# PC_ESP8266_Shield.net
KiCad netlist of a schematic drawn in EAGLE
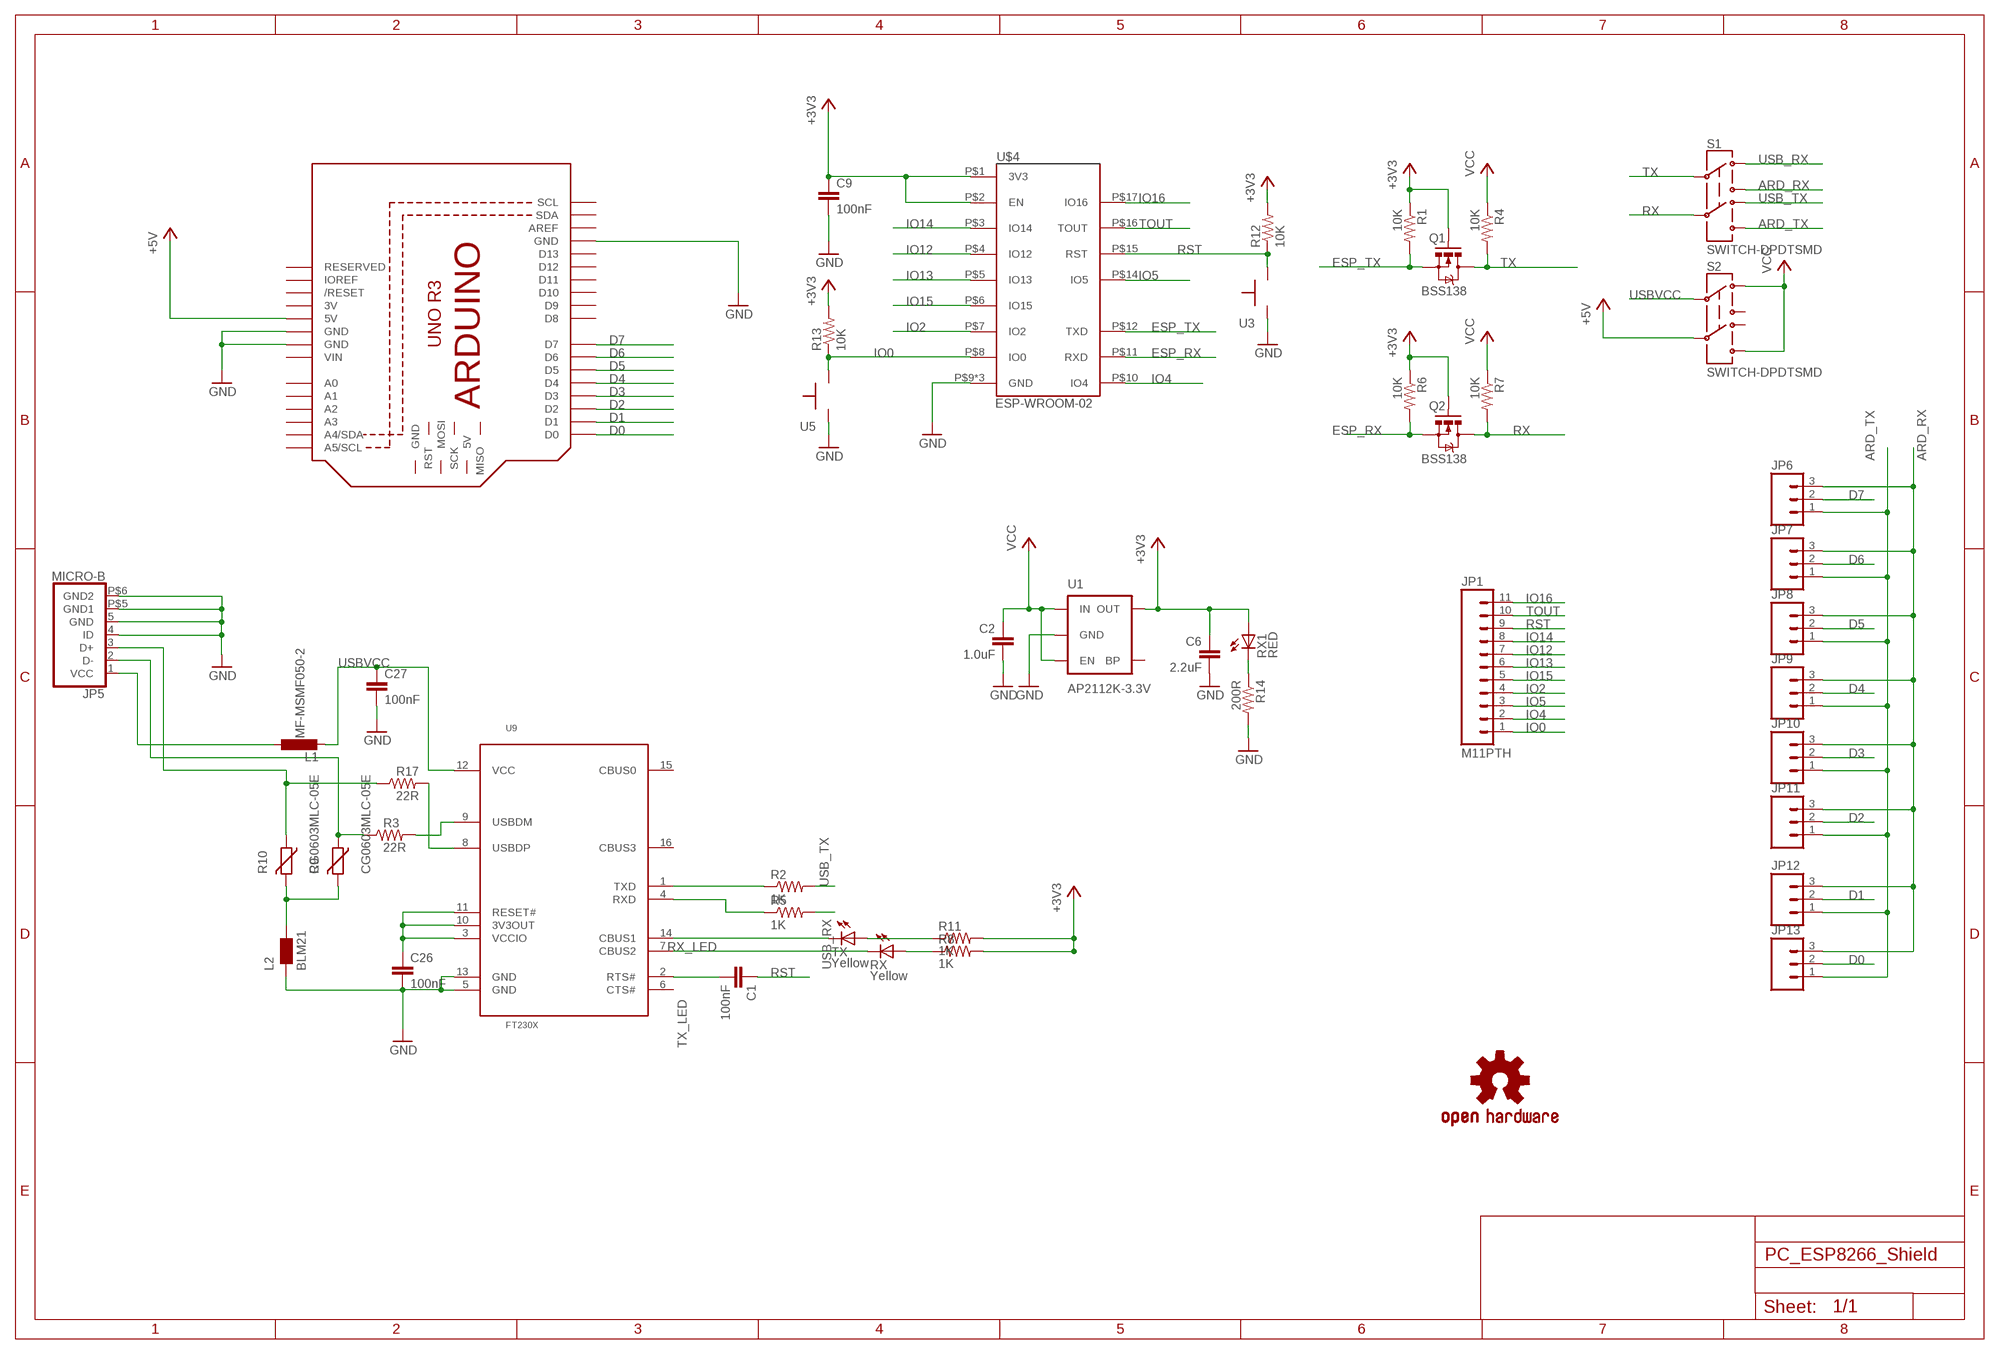
[diagram p0: schematic, sheet 1]

(export (version "E")
  (design (tool "Eeschema 10.0.6"))
  (components
    (comp (ref "C1")
      (value "100nF")
      (footprint "eagle-import:C0805")
      (libsource (lib "eagle-import") (part "C-EUC0805"))
    )
    (comp (ref "C2")
      (value "1.0uF")
      (footprint "eagle-import:0805")
      (libsource (lib "eagle-import") (part "1.0UF-25V-+80/-20(0805)"))
    )
    (comp (ref "C6")
      (value "2.2uF")
      (footprint "eagle-import:C0805")
      (libsource (lib "eagle-import") (part "C-EUC0805"))
    )
    (comp (ref "C9")
      (value "100nF")
      (footprint "eagle-import:C0805")
      (libsource (lib "eagle-import") (part "C-EUC0805"))
    )
    (comp (ref "C26")
      (value "100nF")
      (footprint "eagle-import:C0805")
      (libsource (lib "eagle-import") (part "C-EUC0805"))
    )
    (comp (ref "C27")
      (value "100nF")
      (footprint "eagle-import:C0805")
      (libsource (lib "eagle-import") (part "C-EUC0805"))
    )
    (comp (ref "JP1")
      (value "M11PTH")
      (footprint "eagle-import:1X11")
      (libsource (lib "eagle-import") (part "M11PTH"))
    )
    (comp (ref "JP5")
      (value "MICRO-B")
      (footprint "eagle-import:MICRO-B")
      (libsource (lib "eagle-import") (part "MICRO-B"))
    )
    (comp (ref "JP6")
      (value "M03PTH")
      (footprint "eagle-import:1X03")
      (libsource (lib "eagle-import") (part "M03PTH"))
    )
    (comp (ref "JP7")
      (value "M03PTH")
      (footprint "eagle-import:1X03")
      (libsource (lib "eagle-import") (part "M03PTH"))
    )
    (comp (ref "JP8")
      (value "M03PTH")
      (footprint "eagle-import:1X03")
      (libsource (lib "eagle-import") (part "M03PTH"))
    )
    (comp (ref "JP9")
      (value "M03PTH")
      (footprint "eagle-import:1X03")
      (libsource (lib "eagle-import") (part "M03PTH"))
    )
    (comp (ref "JP10")
      (value "M03PTH")
      (footprint "eagle-import:1X03")
      (libsource (lib "eagle-import") (part "M03PTH"))
    )
    (comp (ref "JP11")
      (value "M03PTH")
      (footprint "eagle-import:1X03")
      (libsource (lib "eagle-import") (part "M03PTH"))
    )
    (comp (ref "JP12")
      (value "M03PTH")
      (footprint "eagle-import:1X03")
      (libsource (lib "eagle-import") (part "M03PTH"))
    )
    (comp (ref "JP13")
      (value "M03PTH")
      (footprint "eagle-import:1X03")
      (libsource (lib "eagle-import") (part "M03PTH"))
    )
    (comp (ref "L1")
      (value "MF-MSMF050-2")
      (footprint "eagle-import:L1812")
      (libsource (lib "eagle-import") (part "L-EUL1812"))
    )
    (comp (ref "L2")
      (value "BLM21")
      (footprint "eagle-import:0805")
      (libsource (lib "eagle-import") (part "WE-CBF_0805"))
    )
    (comp (ref "Q1")
      (value "BSS138")
      (footprint "eagle-import:SOT23-3")
      (libsource (lib "eagle-import") (part "MOSFET-NCHANNELSMD"))
    )
    (comp (ref "Q2")
      (value "BSS138")
      (footprint "eagle-import:SOT23-3")
      (libsource (lib "eagle-import") (part "MOSFET-NCHANNELSMD"))
    )
    (comp (ref "R1")
      (value "10K")
      (footprint "eagle-import:R0805")
      (libsource (lib "eagle-import") (part "R-US_R0805"))
    )
    (comp (ref "R2")
      (value "1K")
      (footprint "eagle-import:R0805")
      (libsource (lib "eagle-import") (part "R-US_R0805"))
    )
    (comp (ref "R3")
      (value "22R")
      (footprint "eagle-import:R0805")
      (libsource (lib "eagle-import") (part "R-US_R0805"))
    )
    (comp (ref "R4")
      (value "10K")
      (footprint "eagle-import:R0805")
      (libsource (lib "eagle-import") (part "R-US_R0805"))
    )
    (comp (ref "R5")
      (value "1K")
      (footprint "eagle-import:R0805")
      (libsource (lib "eagle-import") (part "R-US_R0805"))
    )
    (comp (ref "R6")
      (value "10K")
      (footprint "eagle-import:R0805")
      (libsource (lib "eagle-import") (part "R-US_R0805"))
    )
    (comp (ref "R7")
      (value "10K")
      (footprint "eagle-import:R0805")
      (libsource (lib "eagle-import") (part "R-US_R0805"))
    )
    (comp (ref "R8")
      (value "1K")
      (footprint "eagle-import:R0805")
      (libsource (lib "eagle-import") (part "R-US_R0805"))
    )
    (comp (ref "R9")
      (value "CG0603MLC-05E")
      (footprint "eagle-import:CT_CN0603")
      (libsource (lib "eagle-import") (part "VARISTORCN0603"))
    )
    (comp (ref "R10")
      (value "CG0603MLC-05E")
      (footprint "eagle-import:CT_CN0603")
      (libsource (lib "eagle-import") (part "VARISTORCN0603"))
    )
    (comp (ref "R11")
      (value "1K")
      (footprint "eagle-import:R0805")
      (libsource (lib "eagle-import") (part "R-US_R0805"))
    )
    (comp (ref "R12")
      (value "10K")
      (footprint "eagle-import:R0805")
      (libsource (lib "eagle-import") (part "R-US_R0805"))
    )
    (comp (ref "R13")
      (value "10K")
      (footprint "eagle-import:R0805")
      (libsource (lib "eagle-import") (part "R-US_R0805"))
    )
    (comp (ref "R14")
      (value "200R")
      (footprint "eagle-import:R0805")
      (libsource (lib "eagle-import") (part "R-US_R0805"))
    )
    (comp (ref "R17")
      (value "22R")
      (footprint "eagle-import:R0805")
      (libsource (lib "eagle-import") (part "R-US_R0805"))
    )
    (comp (ref "RX")
      (value "Yellow")
      (footprint "eagle-import:CHIPLED_0603")
      (libsource (lib "eagle-import") (part "LEDCHIPLED_0603"))
    )
    (comp (ref "RX1")
      (value "RED")
      (footprint "eagle-import:CHIPLED_0603")
      (libsource (lib "eagle-import") (part "LEDCHIPLED_0603"))
    )
    (comp (ref "S1")
      (value "SWITCH-DPDTSMD")
      (footprint "eagle-import:AYZ0202")
      (libsource (lib "eagle-import") (part "SWITCH-DPDTSMD"))
    )
    (comp (ref "S2")
      (value "SWITCH-DPDTSMD")
      (footprint "eagle-import:AYZ0202")
      (libsource (lib "eagle-import") (part "SWITCH-DPDTSMD"))
    )
    (comp (ref "TX")
      (value "Yellow")
      (footprint "eagle-import:CHIPLED_0603")
      (libsource (lib "eagle-import") (part "LEDCHIPLED_0603"))
    )
    (comp (ref "U$1")
      (value "ARDUINO")
      (footprint "eagle-import:ARDUINO")
      (libsource (lib "eagle-import") (part "ARDUINO"))
    )
    (comp (ref "U$3")
      (value "PROTY-LOGO")
      (footprint "eagle-import:LOGO-PROTY")
      (libsource (lib "eagle-import") (part "PROTY-LOGO"))
    )
    (comp (ref "U$4")
      (value "ESP-WROOM-02")
      (footprint "eagle-import:ESP-WROOM-02")
      (libsource (lib "eagle-import") (part "ESP-WROOM-02"))
    )
    (comp (ref "U$5")
      (value "OSHW-LOGOS")
      (footprint "eagle-import:OSHW-LOGO-S")
      (libsource (lib "eagle-import") (part "OSHW-LOGOS"))
    )
    (comp (ref "U1")
      (value "AP2112K-3.3V")
      (footprint "eagle-import:SOT23-5")
      (libsource (lib "eagle-import") (part "V_REG_LDOSMD"))
    )
    (comp (ref "U3")
      (value "B3U-1000P")
      (footprint "eagle-import:B3U-1000P")
      (libsource (lib "eagle-import") (part "B3U-1000P"))
    )
    (comp (ref "U5")
      (value "B3U-1000P")
      (footprint "eagle-import:B3U-1000P")
      (libsource (lib "eagle-import") (part "B3U-1000P"))
    )
    (comp (ref "U9")
      (value "FT230X")
      (footprint "eagle-import:SSOP_16")
      (libsource (lib "eagle-import") (part "FT230X"))
    )
  )
  (nets
    (net (code "1") (name "+3V3") (class "Default")
      (node (ref "C6") (pin "1") (pinfunction "1_1") (pintype "passive"))
      (node (ref "C9") (pin "1") (pinfunction "1_1") (pintype "passive"))
      (node (ref "Q1") (pin "1") (pinfunction "G_1") (pintype "passive"))
      (node (ref "Q2") (pin "1") (pinfunction "G_1") (pintype "passive"))
      (node (ref "R1") (pin "1") (pinfunction "1_1") (pintype "passive"))
      (node (ref "R11") (pin "2") (pinfunction "2_2") (pintype "passive"))
      (node (ref "R12") (pin "2") (pinfunction "2_2") (pintype "passive"))
      (node (ref "R13") (pin "2") (pinfunction "2_2") (pintype "passive"))
      (node (ref "R6") (pin "1") (pinfunction "1_1") (pintype "passive"))
      (node (ref "R8") (pin "2") (pinfunction "2_2") (pintype "passive"))
      (node (ref "RX1") (pin "A") (pinfunction "A_A") (pintype "passive"))
      (node (ref "U$4") (pin "P$1") (pinfunction "3V3_P$1") (pintype "power_in"))
      (node (ref "U$4") (pin "P$2") (pinfunction "EN_P$2") (pintype "bidirectional"))
      (node (ref "U1") (pin "5") (pinfunction "OUT_5") (pintype "passive"))
    )
    (net (code "2") (name "+5V") (class "Default")
      (node (ref "S2") (pin "5") (pinfunction "5_5") (pintype "bidirectional"))
      (node (ref "U$1") (pin "5V") (pinfunction "5V_5V") (pintype "power_in"))
    )
    (net (code "3") (name "/3V") (class "Default")
      (node (ref "U$1") (pin "3V") (pinfunction "3V_3V") (pintype "power_in"))
    )
    (net (code "4") (name "/ARD_RX") (class "Default")
      (node (ref "JP10") (pin "3") (pinfunction "3_3") (pintype "passive"))
      (node (ref "JP11") (pin "3") (pinfunction "3_3") (pintype "passive"))
      (node (ref "JP12") (pin "3") (pinfunction "3_3") (pintype "passive"))
      (node (ref "JP13") (pin "3") (pinfunction "3_3") (pintype "passive"))
      (node (ref "JP6") (pin "3") (pinfunction "3_3") (pintype "passive"))
      (node (ref "JP7") (pin "3") (pinfunction "3_3") (pintype "passive"))
      (node (ref "JP8") (pin "3") (pinfunction "3_3") (pintype "passive"))
      (node (ref "JP9") (pin "3") (pinfunction "3_3") (pintype "passive"))
      (node (ref "S1") (pin "3") (pinfunction "3_3") (pintype "bidirectional"))
    )
    (net (code "5") (name "/ARD_TX") (class "Default")
      (node (ref "JP10") (pin "1") (pinfunction "1_1") (pintype "passive"))
      (node (ref "JP11") (pin "1") (pinfunction "1_1") (pintype "passive"))
      (node (ref "JP12") (pin "1") (pinfunction "1_1") (pintype "passive"))
      (node (ref "JP13") (pin "1") (pinfunction "1_1") (pintype "passive"))
      (node (ref "JP6") (pin "1") (pinfunction "1_1") (pintype "passive"))
      (node (ref "JP7") (pin "1") (pinfunction "1_1") (pintype "passive"))
      (node (ref "JP8") (pin "1") (pinfunction "1_1") (pintype "passive"))
      (node (ref "JP9") (pin "1") (pinfunction "1_1") (pintype "passive"))
      (node (ref "S1") (pin "6") (pinfunction "6_6") (pintype "bidirectional"))
    )
    (net (code "6") (name "/D0") (class "Default")
      (node (ref "JP13") (pin "2") (pinfunction "2_2") (pintype "passive"))
      (node (ref "U$1") (pin "D0") (pinfunction "D0_D0") (pintype "bidirectional"))
    )
    (net (code "7") (name "/D1") (class "Default")
      (node (ref "JP12") (pin "2") (pinfunction "2_2") (pintype "passive"))
      (node (ref "U$1") (pin "D1") (pinfunction "D1_D1") (pintype "bidirectional"))
    )
    (net (code "8") (name "/D2") (class "Default")
      (node (ref "JP11") (pin "2") (pinfunction "2_2") (pintype "passive"))
      (node (ref "U$1") (pin "D2") (pinfunction "D2_D2") (pintype "bidirectional"))
    )
    (net (code "9") (name "/D3") (class "Default")
      (node (ref "JP10") (pin "2") (pinfunction "2_2") (pintype "passive"))
      (node (ref "U$1") (pin "D3") (pinfunction "D3_D3") (pintype "bidirectional"))
    )
    (net (code "10") (name "/D4") (class "Default")
      (node (ref "JP9") (pin "2") (pinfunction "2_2") (pintype "passive"))
      (node (ref "U$1") (pin "D4") (pinfunction "D4_D4") (pintype "bidirectional"))
    )
    (net (code "11") (name "/D5") (class "Default")
      (node (ref "JP8") (pin "2") (pinfunction "2_2") (pintype "passive"))
      (node (ref "U$1") (pin "D5") (pinfunction "D5_D5") (pintype "bidirectional"))
    )
    (net (code "12") (name "/D6") (class "Default")
      (node (ref "JP7") (pin "2") (pinfunction "2_2") (pintype "passive"))
      (node (ref "U$1") (pin "D6") (pinfunction "D6_D6") (pintype "bidirectional"))
    )
    (net (code "13") (name "/D7") (class "Default")
      (node (ref "JP6") (pin "2") (pinfunction "2_2") (pintype "passive"))
      (node (ref "U$1") (pin "D7") (pinfunction "D7_D7") (pintype "bidirectional"))
    )
    (net (code "14") (name "/ESP_RX") (class "Default")
      (node (ref "Q2") (pin "2") (pinfunction "S_2") (pintype "passive"))
      (node (ref "R6") (pin "2") (pinfunction "2_2") (pintype "passive"))
      (node (ref "U$4") (pin "P$11") (pinfunction "RXD_P$11") (pintype "input"))
    )
    (net (code "15") (name "/ESP_TX") (class "Default")
      (node (ref "Q1") (pin "2") (pinfunction "S_2") (pintype "passive"))
      (node (ref "R1") (pin "2") (pinfunction "2_2") (pintype "passive"))
      (node (ref "U$4") (pin "P$12") (pinfunction "TXD_P$12") (pintype "output"))
    )
    (net (code "16") (name "/IO0") (class "Default")
      (node (ref "JP1") (pin "1") (pinfunction "1_1") (pintype "passive"))
      (node (ref "R13") (pin "1") (pinfunction "1_1") (pintype "passive"))
      (node (ref "U$4") (pin "P$8") (pinfunction "IO0_P$8") (pintype "bidirectional"))
      (node (ref "U5") (pin "P$2") (pinfunction "P$2_P$2") (pintype "bidirectional"))
    )
    (net (code "17") (name "/IO2") (class "Default")
      (node (ref "JP1") (pin "4") (pinfunction "4_4") (pintype "passive"))
      (node (ref "U$4") (pin "P$7") (pinfunction "IO2_P$7") (pintype "bidirectional"))
    )
    (net (code "18") (name "/IO4") (class "Default")
      (node (ref "JP1") (pin "2") (pinfunction "2_2") (pintype "passive"))
      (node (ref "U$4") (pin "P$10") (pinfunction "IO4_P$10") (pintype "bidirectional"))
    )
    (net (code "19") (name "/IO5") (class "Default")
      (node (ref "JP1") (pin "3") (pinfunction "3_3") (pintype "passive"))
      (node (ref "U$4") (pin "P$14") (pinfunction "IO5_P$14") (pintype "bidirectional"))
    )
    (net (code "20") (name "/IO12") (class "Default")
      (node (ref "JP1") (pin "7") (pinfunction "7_7") (pintype "passive"))
      (node (ref "U$4") (pin "P$4") (pinfunction "IO12_P$4") (pintype "bidirectional"))
    )
    (net (code "21") (name "/IO13") (class "Default")
      (node (ref "JP1") (pin "6") (pinfunction "6_6") (pintype "passive"))
      (node (ref "U$4") (pin "P$5") (pinfunction "IO13_P$5") (pintype "bidirectional"))
    )
    (net (code "22") (name "/IO14") (class "Default")
      (node (ref "JP1") (pin "8") (pinfunction "8_8") (pintype "passive"))
      (node (ref "U$4") (pin "P$3") (pinfunction "IO14_P$3") (pintype "bidirectional"))
    )
    (net (code "23") (name "/IO15") (class "Default")
      (node (ref "JP1") (pin "5") (pinfunction "5_5") (pintype "passive"))
      (node (ref "U$4") (pin "P$6") (pinfunction "IO15_P$6") (pintype "bidirectional"))
    )
    (net (code "24") (name "/IO16") (class "Default")
      (node (ref "JP1") (pin "11") (pinfunction "11_11") (pintype "passive"))
      (node (ref "U$4") (pin "P$17") (pinfunction "IO16_P$17") (pintype "bidirectional"))
    )
    (net (code "25") (name "/RST") (class "Default")
      (node (ref "C1") (pin "1") (pinfunction "1_1") (pintype "passive"))
      (node (ref "JP1") (pin "9") (pinfunction "9_9") (pintype "passive"))
      (node (ref "R12") (pin "1") (pinfunction "1_1") (pintype "passive"))
      (node (ref "U$4") (pin "P$15") (pinfunction "RST_P$15") (pintype "bidirectional"))
      (node (ref "U3") (pin "P$2") (pinfunction "P$2_P$2") (pintype "bidirectional"))
    )
    (net (code "26") (name "/RX") (class "Default")
      (node (ref "Q2") (pin "3") (pinfunction "D_3") (pintype "passive"))
      (node (ref "R7") (pin "2") (pinfunction "2_2") (pintype "passive"))
      (node (ref "S1") (pin "5") (pinfunction "5_5") (pintype "bidirectional"))
    )
    (net (code "27") (name "/RX_LED") (class "Default")
      (node (ref "RX") (pin "C") (pinfunction "C_C") (pintype "passive"))
      (node (ref "U9") (pin "7") (pinfunction "CBUS2_7") (pintype "bidirectional"))
    )
    (net (code "28") (name "/TOUT") (class "Default")
      (node (ref "JP1") (pin "10") (pinfunction "10_10") (pintype "passive"))
      (node (ref "U$4") (pin "P$16") (pinfunction "TOUT_P$16") (pintype "bidirectional"))
    )
    (net (code "29") (name "/TX") (class "Default")
      (node (ref "Q1") (pin "3") (pinfunction "D_3") (pintype "passive"))
      (node (ref "R4") (pin "2") (pinfunction "2_2") (pintype "passive"))
      (node (ref "S1") (pin "2") (pinfunction "2_2") (pintype "bidirectional"))
    )
    (net (code "30") (name "/TX_LED") (class "Default")
      (node (ref "TX") (pin "C") (pinfunction "C_C") (pintype "passive"))
      (node (ref "U9") (pin "14") (pinfunction "CBUS1_14") (pintype "bidirectional"))
    )
    (net (code "31") (name "/USBVCC") (class "Default")
      (node (ref "C27") (pin "1") (pinfunction "1_1") (pintype "passive"))
      (node (ref "L1") (pin "2") (pinfunction "2_2") (pintype "passive"))
      (node (ref "S2") (pin "2") (pinfunction "2_2") (pintype "bidirectional"))
      (node (ref "U9") (pin "12") (pinfunction "VCC_12") (pintype "bidirectional"))
    )
    (net (code "32") (name "/USB_RX") (class "Default")
      (node (ref "R5") (pin "2") (pinfunction "2_2") (pintype "passive"))
      (node (ref "S1") (pin "1") (pinfunction "1_1") (pintype "bidirectional"))
    )
    (net (code "33") (name "/USB_TX") (class "Default")
      (node (ref "R2") (pin "2") (pinfunction "2_2") (pintype "passive"))
      (node (ref "S1") (pin "4") (pinfunction "4_4") (pintype "bidirectional"))
    )
    (net (code "34") (name "/VIN") (class "Default")
      (node (ref "U$1") (pin "VIN") (pinfunction "VIN_VIN") (pintype "power_in"))
    )
    (net (code "35") (name "GND") (class "Default")
      (node (ref "C2") (pin "2") (pinfunction "2_2") (pintype "passive"))
      (node (ref "C26") (pin "2") (pinfunction "2_2") (pintype "passive"))
      (node (ref "C27") (pin "2") (pinfunction "2_2") (pintype "passive"))
      (node (ref "C6") (pin "2") (pinfunction "2_2") (pintype "passive"))
      (node (ref "C9") (pin "2") (pinfunction "2_2") (pintype "passive"))
      (node (ref "JP5") (pin "4") (pinfunction "ID_4") (pintype "bidirectional"))
      (node (ref "JP5") (pin "5") (pinfunction "GND_5") (pintype "bidirectional"))
      (node (ref "JP5") (pin "P$5") (pinfunction "GND1_P$5") (pintype "bidirectional"))
      (node (ref "JP5") (pin "P$6") (pinfunction "GND2_P$6") (pintype "bidirectional"))
      (node (ref "L2") (pin "1") (pinfunction "1_1") (pintype "passive"))
      (node (ref "R14") (pin "2") (pinfunction "2_2") (pintype "passive"))
      (node (ref "U$1") (pin "GND") (pinfunction "GND_GND") (pintype "power_in"))
      (node (ref "U$1") (pin "GND@1") (pinfunction "GND_GND@1") (pintype "power_in"))
      (node (ref "U$1") (pin "GND@2") (pinfunction "GND_GND@2") (pintype "power_in"))
      (node (ref "U$4") (pin "P$13") (pinfunction "GND_P$13") (pintype "power_in"))
      (node (ref "U$4") (pin "P$18") (pinfunction "GND_P$18") (pintype "power_in"))
      (node (ref "U$4") (pin "P$9") (pinfunction "GND_P$9") (pintype "power_in"))
      (node (ref "U1") (pin "2") (pinfunction "GND_2") (pintype "input"))
      (node (ref "U3") (pin "P$1") (pinfunction "P$1_P$1") (pintype "bidirectional"))
      (node (ref "U5") (pin "P$1") (pinfunction "P$1_P$1") (pintype "bidirectional"))
      (node (ref "U9") (pin "13") (pinfunction "GND_13") (pintype "bidirectional"))
      (node (ref "U9") (pin "5") (pinfunction "GND_5") (pintype "bidirectional"))
    )
    (net (code "36") (name "Net-(JP5-D+)") (class "Default")
      (node (ref "JP5") (pin "3") (pinfunction "D+_3") (pintype "bidirectional"))
      (node (ref "R10") (pin "1") (pinfunction "1_1") (pintype "passive"))
      (node (ref "R17") (pin "1") (pinfunction "1_1") (pintype "passive"))
    )
    (net (code "37") (name "Net-(JP5-D-)") (class "Default")
      (node (ref "JP5") (pin "2") (pinfunction "D-_2") (pintype "bidirectional"))
      (node (ref "R3") (pin "1") (pinfunction "1_1") (pintype "passive"))
      (node (ref "R9") (pin "1") (pinfunction "1_1") (pintype "passive"))
    )
    (net (code "38") (name "Net-(JP5-VCC)") (class "Default")
      (node (ref "JP5") (pin "1") (pinfunction "VCC_1") (pintype "bidirectional"))
      (node (ref "L1") (pin "1") (pinfunction "1_1") (pintype "passive"))
    )
    (net (code "39") (name "Net-(L2-Pad2)") (class "Default")
      (node (ref "L2") (pin "2") (pinfunction "2_2") (pintype "passive"))
      (node (ref "R10") (pin "2") (pinfunction "2_2") (pintype "passive"))
      (node (ref "R9") (pin "2") (pinfunction "2_2") (pintype "passive"))
    )
    (net (code "40") (name "Net-(R8-Pad1)") (class "Default")
      (node (ref "R8") (pin "1") (pinfunction "1_1") (pintype "passive"))
      (node (ref "RX") (pin "A") (pinfunction "A_A") (pintype "passive"))
    )
    (net (code "41") (name "Net-(R11-Pad1)") (class "Default")
      (node (ref "R11") (pin "1") (pinfunction "1_1") (pintype "passive"))
      (node (ref "TX") (pin "A") (pinfunction "A_A") (pintype "passive"))
    )
    (net (code "42") (name "Net-(R14-Pad1)") (class "Default")
      (node (ref "R14") (pin "1") (pinfunction "1_1") (pintype "passive"))
      (node (ref "RX1") (pin "C") (pinfunction "C_C") (pintype "passive"))
    )
    (net (code "43") (name "Net-(U9-3V3OUT)") (class "Default")
      (node (ref "C26") (pin "1") (pinfunction "1_1") (pintype "passive"))
      (node (ref "U9") (pin "10") (pinfunction "3V3OUT_10") (pintype "bidirectional"))
      (node (ref "U9") (pin "11") (pinfunction "RESET#_11") (pintype "bidirectional"))
      (node (ref "U9") (pin "3") (pinfunction "VCCIO_3") (pintype "bidirectional"))
    )
    (net (code "44") (name "Net-(U9-RTS#)") (class "Default")
      (node (ref "C1") (pin "2") (pinfunction "2_2") (pintype "passive"))
      (node (ref "U9") (pin "2") (pinfunction "RTS#_2") (pintype "bidirectional"))
    )
    (net (code "45") (name "Net-(U9-RXD)") (class "Default")
      (node (ref "R5") (pin "1") (pinfunction "1_1") (pintype "passive"))
      (node (ref "U9") (pin "4") (pinfunction "RXD_4") (pintype "bidirectional"))
    )
    (net (code "46") (name "Net-(U9-TXD)") (class "Default")
      (node (ref "R2") (pin "1") (pinfunction "1_1") (pintype "passive"))
      (node (ref "U9") (pin "1") (pinfunction "TXD_1") (pintype "bidirectional"))
    )
    (net (code "47") (name "Net-(U9-USBDM)") (class "Default")
      (node (ref "R3") (pin "2") (pinfunction "2_2") (pintype "passive"))
      (node (ref "U9") (pin "9") (pinfunction "USBDM_9") (pintype "bidirectional"))
    )
    (net (code "48") (name "Net-(U9-USBDP)") (class "Default")
      (node (ref "R17") (pin "2") (pinfunction "2_2") (pintype "passive"))
      (node (ref "U9") (pin "8") (pinfunction "USBDP_8") (pintype "bidirectional"))
    )
    (net (code "49") (name "VCC") (class "Default")
      (node (ref "C2") (pin "1") (pinfunction "1_1") (pintype "passive"))
      (node (ref "R4") (pin "1") (pinfunction "1_1") (pintype "passive"))
      (node (ref "R7") (pin "1") (pinfunction "1_1") (pintype "passive"))
      (node (ref "S2") (pin "1") (pinfunction "1_1") (pintype "bidirectional"))
      (node (ref "S2") (pin "6") (pinfunction "6_6") (pintype "bidirectional"))
      (node (ref "U1") (pin "1") (pinfunction "IN_1") (pintype "input"))
      (node (ref "U1") (pin "3") (pinfunction "EN_3") (pintype "input"))
    )
    (net (code "50") (name "unconnected-(S2-Pad3)") (class "Default")
      (node (ref "S2") (pin "3") (pinfunction "3_3") (pintype "bidirectional"))
    )
    (net (code "51") (name "unconnected-(S2-Pad4)") (class "Default")
      (node (ref "S2") (pin "4") (pinfunction "4_4") (pintype "bidirectional"))
    )
    (net (code "52") (name "unconnected-(U$1-5V-Pad5V_ICSP)") (class "Default")
      (node (ref "U$1") (pin "5V_ICSP") (pinfunction "5V_5V_ICSP") (pintype "passive"))
    )
    (net (code "53") (name "unconnected-(U$1-A4{slash}SDA-PadA4)") (class "Default")
      (node (ref "U$1") (pin "A4") (pinfunction "A4/SDA_A4") (pintype "bidirectional"))
    )
    (net (code "54") (name "unconnected-(U$1-A5{slash}SCL-PadA5)") (class "Default")
      (node (ref "U$1") (pin "A5") (pinfunction "A5/SCL_A5") (pintype "bidirectional"))
    )
    (net (code "55") (name "unconnected-(U$1-GND-PadGND@3)") (class "Default")
      (node (ref "U$1") (pin "GND@3") (pinfunction "GND_GND@3") (pintype "passive"))
    )
    (net (code "56") (name "unconnected-(U$1-PadA0)") (class "Default")
      (node (ref "U$1") (pin "A0") (pinfunction "A0_A0") (pintype "bidirectional"))
    )
    (net (code "57") (name "unconnected-(U$1-PadA1)") (class "Default")
      (node (ref "U$1") (pin "A1") (pinfunction "A1_A1") (pintype "bidirectional"))
    )
    (net (code "58") (name "unconnected-(U$1-PadA2)") (class "Default")
      (node (ref "U$1") (pin "A2") (pinfunction "A2_A2") (pintype "bidirectional"))
    )
    (net (code "59") (name "unconnected-(U$1-PadA3)") (class "Default")
      (node (ref "U$1") (pin "A3") (pinfunction "A3_A3") (pintype "bidirectional"))
    )
    (net (code "60") (name "unconnected-(U$1-PadAREF)") (class "Default")
      (node (ref "U$1") (pin "AREF") (pinfunction "AREF_AREF") (pintype "bidirectional"))
    )
    (net (code "61") (name "unconnected-(U$1-PadD8)") (class "Default")
      (node (ref "U$1") (pin "D8") (pinfunction "D8_D8") (pintype "bidirectional"))
    )
    (net (code "62") (name "unconnected-(U$1-PadD9)") (class "Default")
      (node (ref "U$1") (pin "D9") (pinfunction "D9_D9") (pintype "bidirectional"))
    )
    (net (code "63") (name "unconnected-(U$1-PadD10)") (class "Default")
      (node (ref "U$1") (pin "D10") (pinfunction "D10_D10") (pintype "bidirectional"))
    )
    (net (code "64") (name "unconnected-(U$1-PadD11)") (class "Default")
      (node (ref "U$1") (pin "D11") (pinfunction "D11_D11") (pintype "bidirectional"))
    )
    (net (code "65") (name "unconnected-(U$1-PadD12)") (class "Default")
      (node (ref "U$1") (pin "D12") (pinfunction "D12_D12") (pintype "bidirectional"))
    )
    (net (code "66") (name "unconnected-(U$1-PadD13)") (class "Default")
      (node (ref "U$1") (pin "D13") (pinfunction "D13_D13") (pintype "bidirectional"))
    )
    (net (code "67") (name "unconnected-(U$1-PadIOREF)") (class "Default")
      (node (ref "U$1") (pin "IOREF") (pinfunction "IOREF_IOREF") (pintype "output"))
    )
    (net (code "68") (name "unconnected-(U$1-PadMISO)") (class "Default")
      (node (ref "U$1") (pin "MISO") (pinfunction "MISO_MISO") (pintype "passive"))
    )
    (net (code "69") (name "unconnected-(U$1-PadMOSI)") (class "Default")
      (node (ref "U$1") (pin "MOSI") (pinfunction "MOSI_MOSI") (pintype "passive"))
    )
    (net (code "70") (name "unconnected-(U$1-PadRESERVED)") (class "Default")
      (node (ref "U$1") (pin "RESERVED") (pinfunction "RESERVED_RESERVED") (pintype "no_connect"))
    )
    (net (code "71") (name "unconnected-(U$1-PadSCK)") (class "Default")
      (node (ref "U$1") (pin "SCK") (pinfunction "SCK_SCK") (pintype "passive"))
    )
    (net (code "72") (name "unconnected-(U$1-PadSCL)") (class "Default")
      (node (ref "U$1") (pin "SCL") (pinfunction "SCL_SCL") (pintype "bidirectional"))
    )
    (net (code "73") (name "unconnected-(U$1-PadSDA)") (class "Default")
      (node (ref "U$1") (pin "SDA") (pinfunction "SDA_SDA") (pintype "bidirectional"))
    )
    (net (code "74") (name "unconnected-(U$1-RST-PadRESET_ICSP)") (class "Default")
      (node (ref "U$1") (pin "RESET_ICSP") (pinfunction "RST_RESET_ICSP") (pintype "passive"))
    )
    (net (code "75") (name "unconnected-(U$1-{slash}RESET-PadRESET)") (class "Default")
      (node (ref "U$1") (pin "RESET") (pinfunction "/RESET_RESET") (pintype "bidirectional"))
    )
    (net (code "76") (name "unconnected-(U1-BP-Pad4)") (class "Default")
      (node (ref "U1") (pin "4") (pinfunction "BP_4") (pintype "input"))
    )
    (net (code "77") (name "unconnected-(U9-CBUS0-Pad15)") (class "Default")
      (node (ref "U9") (pin "15") (pinfunction "CBUS0_15") (pintype "bidirectional"))
    )
    (net (code "78") (name "unconnected-(U9-CBUS3-Pad16)") (class "Default")
      (node (ref "U9") (pin "16") (pinfunction "CBUS3_16") (pintype "bidirectional"))
    )
    (net (code "79") (name "unconnected-(U9-CTS#-Pad6)") (class "Default")
      (node (ref "U9") (pin "6") (pinfunction "CTS#_6") (pintype "bidirectional"))
    )
  )
)
